# 06_-_3V3_VOLTAGE_REGULATOR.net
KiCad netlist of a schematic drawn in Altium Designer
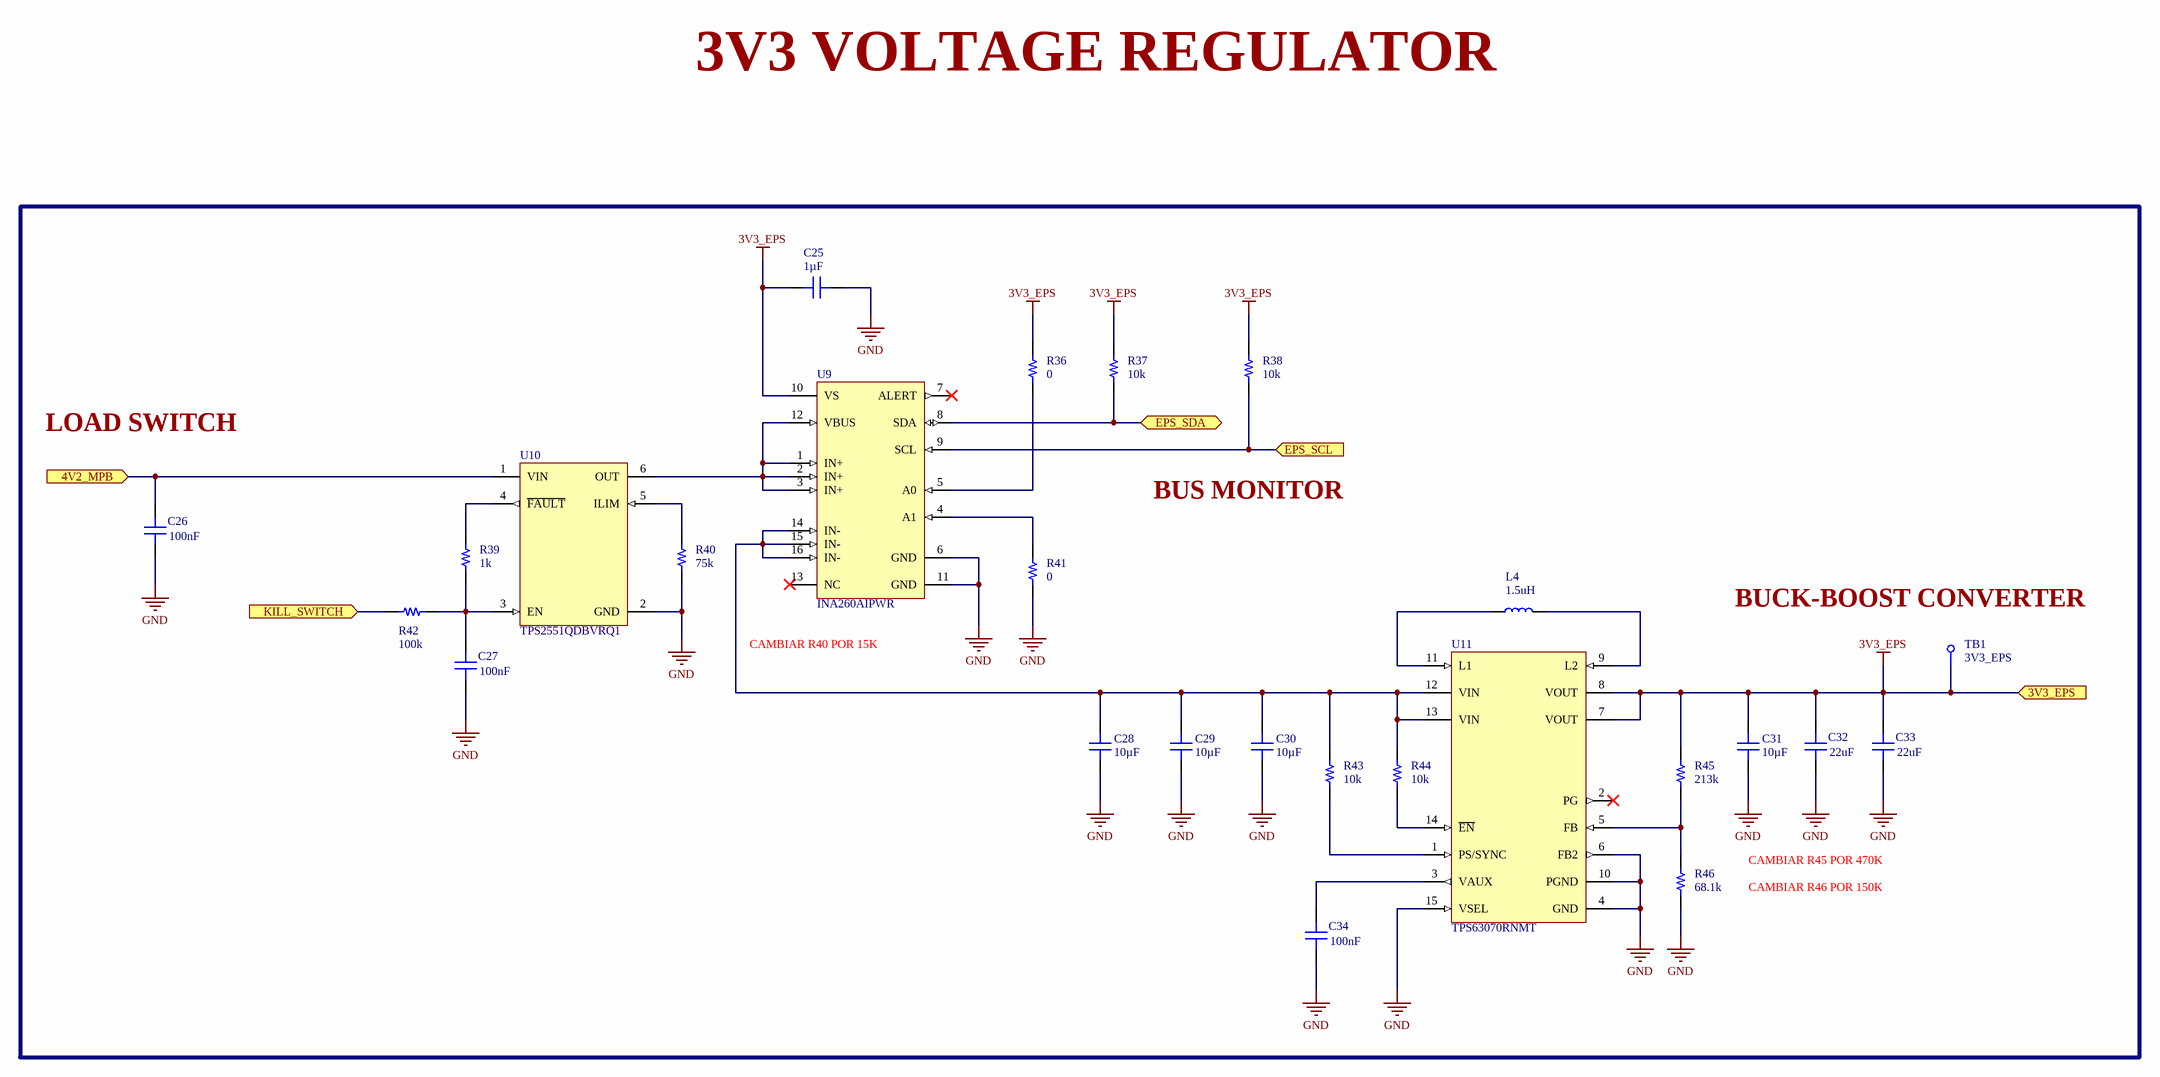
[diagram p0: [06] - 3V3 VOLTAGE REGULATOR.SchDoc]

(export (version "E")
  (design (tool "Eeschema 10.0.6"))
  (components
    (comp (ref "C25")
      (value "CL10A105KP8NNNC")
      (footprint "CAP 0603/1608")
      (description "CAP CER 1UF 10V X5R 0603")
      (fields
        (field (name "MANUFACTURER") "Samsung")
        (field (name "TOLERANCE") "10%")
        (field (name "CAPACITANCE") "1µF")
      )
      (libsource (lib "UVG") (part "CL10A105KP8NNNC"))
    )
    (comp (ref "C26")
      (value "C0603C104K8RACTU")
      (footprint "CAP 0603/1608")
      (description "CAP CER 0.1UF 10V X7R 0603")
      (fields
        (field (name "MANUFACTURER") "KEMET")
        (field (name "CAPACITANCE") "100nF")
        (field (name "TOLERANCE") "10%")
      )
      (libsource (lib "UVG") (part "C0603C104K8RACTU"))
    )
    (comp (ref "C27")
      (value "C0603C104K8RACTU")
      (footprint "CAP 0603/1608")
      (description "CAP CER 0.1UF 10V X7R 0603")
      (fields
        (field (name "MANUFACTURER") "KEMET")
        (field (name "CAPACITANCE") "100nF")
        (field (name "TOLERANCE") "10%")
      )
      (libsource (lib "UVG") (part "C0603C104K8RACTU"))
    )
    (comp (ref "C28")
      (value "LMK212BJ106KG-T")
      (footprint "CAP 0805/2012")
      (description "CAP CER 10UF 10V X5R 0805")
      (fields
        (field (name "MANUFACTURER") "Taiyo Yuden")
        (field (name "PCN PART NUMBER") "X5R, X7R Dielectrics 23/Jan/2008")
        (field (name "CAPACITANCE") "10µF")
      )
      (libsource (lib "UVG") (part "LMK212BJ106KG-T"))
    )
    (comp (ref "C29")
      (value "LMK212BJ106KG-T")
      (footprint "CAP 0805/2012")
      (description "CAP CER 10UF 10V X5R 0805")
      (fields
        (field (name "MANUFACTURER") "Taiyo Yuden")
        (field (name "PCN PART NUMBER") "X5R, X7R Dielectrics 23/Jan/2008")
        (field (name "CAPACITANCE") "10µF")
      )
      (libsource (lib "UVG") (part "LMK212BJ106KG-T"))
    )
    (comp (ref "C30")
      (value "CL10A106MQ8NNNC")
      (footprint "CAP 0603/1608")
      (description "CAP CER 10UF 6.3V X5R 0603")
      (fields
        (field (name "MANUFACTURER") "Samsung")
        (field (name "CAPACITANCE") "10µF")
        (field (name "TOLERANCE") "20%")
      )
      (libsource (lib "UVG") (part "CL10A106MQ8NNNC"))
    )
    (comp (ref "C31")
      (value "CL10A106MQ8NNNC")
      (footprint "CAP 0603/1608")
      (description "CAP CER 10UF 6.3V X5R 0603")
      (fields
        (field (name "MANUFACTURER") "Samsung")
        (field (name "CAPACITANCE") "10µF")
        (field (name "TOLERANCE") "20%")
      )
      (libsource (lib "UVG") (part "CL10A106MQ8NNNC"))
    )
    (comp (ref "C32")
      (value "CL21A226MQQNNNE")
      (footprint "CAP 0805/2012")
      (description "CAP CER 22UF 6.3V X5R 0805")
      (fields
        (field (name "MANUFACTURER") "Samsung")
        (field (name "CAPACITANCE") "22uF")
        (field (name "TOLERANCE") "20%")
      )
      (libsource (lib "UVG") (part "CL21A226MQQNNNE"))
    )
    (comp (ref "C33")
      (value "CL21A226MQQNNNE")
      (footprint "CAP 0805/2012")
      (description "CAP CER 22UF 6.3V X5R 0805")
      (fields
        (field (name "MANUFACTURER") "Samsung")
        (field (name "CAPACITANCE") "22uF")
        (field (name "TOLERANCE") "20%")
      )
      (libsource (lib "UVG") (part "CL21A226MQQNNNE"))
    )
    (comp (ref "C34")
      (value "C0603C104K8RACTU")
      (footprint "CAP 0603/1608")
      (description "CAP CER 0.1UF 10V X7R 0603")
      (fields
        (field (name "MANUFACTURER") "KEMET")
        (field (name "CAPACITANCE") "100nF")
        (field (name "TOLERANCE") "10%")
      )
      (libsource (lib "UVG") (part "C0603C104K8RACTU"))
    )
    (comp (ref "L4")
      (value "XFL4020-152MEB")
      (footprint "XFL4020")
      (description "FIXED IND 1.5UH 9.1A 15.8 MOHM SMD")
      (fields
        (field (name "MANUFACTURER") "Coilcraft")
        (field (name "TOLERANCE") "20%")
        (field (name "INDUCTANCE") "1.5uH")
      )
      (libsource (lib "UVG") (part "XFL4020-152MEB"))
    )
    (comp (ref "R36")
      (value "RMCF0603ZT0R00")
      (footprint "RES 0603/1608")
      (description "RES SMD 0 OHM JUMPER 1/10W 0603")
      (fields (field (name "MANUFACTURER") "Stackpole Electronics") (field (name "RESISTANCE") "0"))
      (libsource (lib "UVG") (part "RMCF0603ZT0R00"))
    )
    (comp (ref "R37")
      (value "RNCP0603FTD10K0")
      (footprint "RES 0603/1608")
      (description "RES SMD 10K OHM 1% 1/8W 0603")
      (fields
        (field (name "MANUFACTURER") "Stackpole Electronics")
        (field (name "RESISTANCE") "10k")
        (field (name "TOLERANCE") "1%")
      )
      (libsource (lib "UVG") (part "RNCP0603FTD10K0"))
    )
    (comp (ref "R38")
      (value "RNCP0603FTD10K0")
      (footprint "RES 0603/1608")
      (description "RES SMD 10K OHM 1% 1/8W 0603")
      (fields
        (field (name "MANUFACTURER") "Stackpole Electronics")
        (field (name "RESISTANCE") "10k")
        (field (name "TOLERANCE") "1%")
      )
      (libsource (lib "UVG") (part "RNCP0603FTD10K0"))
    )
    (comp (ref "R39")
      (value "ESR03EZPJ102")
      (footprint "RES 0603/1608")
      (description "RES SMD 1K OHM 5% 1/4W 0603")
      (fields
        (field (name "MANUFACTURER") "Rohm")
        (field (name "RESISTANCE") "1k")
        (field (name "TOLERANCE") "5%")
      )
      (libsource (lib "UVG") (part "ESR03EZPJ102"))
    )
    (comp (ref "R40")
      (value "ERJ3EKF7502V")
      (footprint "RES 0603/1608")
      (description "RES SMD 75K OHM 1% 1/10W 0603")
      (fields
        (field (name "MANUFACTURER") "Panasonic")
        (field (name "RESISTANCE") "75k")
        (field (name "TOLERANCE") "1%")
      )
      (libsource (lib "UVG") (part "ERJ3EKF7502V"))
    )
    (comp (ref "R41")
      (value "RMCF0603ZT0R00")
      (footprint "RES 0603/1608")
      (description "RES SMD 0 OHM JUMPER 1/10W 0603")
      (fields (field (name "MANUFACTURER") "Stackpole Electronics") (field (name "RESISTANCE") "0"))
      (libsource (lib "UVG") (part "RMCF0603ZT0R00"))
    )
    (comp (ref "R42")
      (value "CR0603-JW-104ELF")
      (footprint "RES 0603/1608")
      (description "RES SMD 100K OHM 5% 1/10W 0603")
      (fields
        (field (name "MANUFACTURER") "Bourns")
        (field (name "RESISTANCE") "100k")
        (field (name "TOLERANCE") "5%")
      )
      (libsource (lib "UVG") (part "CR0603-JW-104ELF"))
    )
    (comp (ref "R43")
      (value "RC0805FR-0710KL")
      (footprint "RES 0805/2012")
      (description "RES SMD 10K OHM 1% 1/8W 0805")
      (fields
        (field (name "MANUFACTURER") "Yageo")
        (field (name "RESISTANCE") "10k")
        (field (name "TOLERANCE") "1 %")
      )
      (libsource (lib "UVG") (part "RC0805FR-0710KL"))
    )
    (comp (ref "R44")
      (value "RC0805FR-0710KL")
      (footprint "RES 0805/2012")
      (description "RES SMD 10K OHM 1% 1/8W 0805")
      (fields
        (field (name "MANUFACTURER") "Yageo")
        (field (name "RESISTANCE") "10k")
        (field (name "TOLERANCE") "1 %")
      )
      (libsource (lib "UVG") (part "RC0805FR-0710KL"))
    )
    (comp (ref "R45")
      (value "RNCF0603BTE213K")
      (footprint "RES 0603/1608")
      (description "RES SMD 213K OHM 0.1% 1/10W 0603")
      (fields
        (field (name "MANUFACTURER") "Stackpole Electronics")
        (field (name "RESISTANCE") "213k")
        (field (name "TOLERANCE") "0.1%")
      )
      (libsource (lib "UVG") (part "RNCF0603BTE213K"))
    )
    (comp (ref "R46")
      (value "RMCF0603FT68K1")
      (footprint "RES 0603/1608")
      (description "RES SMD 68.1K OHM 1% 1/10W 0603")
      (fields
        (field (name "MANUFACTURER") "Stackpole Electronics")
        (field (name "RESISTANCE") "68.1k")
        (field (name "TOLERANCE") "1%")
      )
      (libsource (lib "UVG") (part "RMCF0603FT68K1"))
    )
    (comp (ref "TB1")
      (value "3V3_EPS")
      (footprint "Testpoint")
      (description "GENERIC TESTPOINT")
      (libsource (lib "UVG") (part "TESTPOINT"))
    )
    (comp (ref "U9")
      (value "INA260AIPWR")
      (footprint "TSOP65P640X120-16N")
      (description "IC MONITOR PWR/CURR 16TSSOP")
      (fields (field (name "MANUFACTURER") "Texas Instruments"))
      (libsource (lib "UVG") (part "INA260AIPWR"))
    )
    (comp (ref "U10")
      (value "TPS2551QDBVRQ1")
      (footprint "SOT23-6")
      (description "IC POWER-DIST SWITCH ADJ SOT23-6")
      (fields (field (name "MANUFACTURER") "Texas Instruments"))
      (libsource (lib "UVG") (part "TPS2551QDBVRQ1"))
    )
    (comp (ref "U11")
      (value "TPS63070RNMT")
      (footprint "15-VQFN-HR")
      (description "IC REG BCK BST ADJ 2A 15VQFN")
      (fields (field (name "MANUFACTURER") "Texas Instruments"))
      (libsource (lib "UVG") (part "TPS63070RNMT"))
    )
  )
  (nets
    (net (code "1") (name "/4V2_MPB") (class "Default")
      (node (ref "C26") (pin "2") (pinfunction "2_2") (pintype "passive"))
      (node (ref "U10") (pin "1") (pinfunction "VIN_1") (pintype "power_in"))
    )
    (net (code "2") (name "/EPS_SCL") (class "Default")
      (node (ref "R38") (pin "1") (pinfunction "1_1") (pintype "passive"))
      (node (ref "U9") (pin "9") (pinfunction "SCL_9") (pintype "input"))
    )
    (net (code "3") (name "/EPS_SDA") (class "Default")
      (node (ref "R37") (pin "1") (pinfunction "1_1") (pintype "passive"))
      (node (ref "U9") (pin "8") (pinfunction "SDA_8") (pintype "bidirectional"))
    )
    (net (code "4") (name "/KILL_SWITCH") (class "Default")
      (node (ref "R42") (pin "1") (pinfunction "1_1") (pintype "passive"))
    )
    (net (code "5") (name "3V3_EPS") (class "Default")
      (node (ref "C25") (pin "1") (pinfunction "1_1") (pintype "passive"))
      (node (ref "C31") (pin "2") (pinfunction "2_2") (pintype "passive"))
      (node (ref "C32") (pin "2") (pinfunction "2_2") (pintype "passive"))
      (node (ref "C33") (pin "2") (pinfunction "2_2") (pintype "passive"))
      (node (ref "R36") (pin "2") (pinfunction "2_2") (pintype "passive"))
      (node (ref "R37") (pin "2") (pinfunction "2_2") (pintype "passive"))
      (node (ref "R38") (pin "2") (pinfunction "2_2") (pintype "passive"))
      (node (ref "R45") (pin "2") (pinfunction "2_2") (pintype "passive"))
      (node (ref "TB1") (pin "1") (pinfunction "1_1") (pintype "passive"))
      (node (ref "U11") (pin "7") (pinfunction "VOUT_7") (pintype "power_in"))
      (node (ref "U11") (pin "8") (pinfunction "VOUT_8") (pintype "power_in"))
      (node (ref "U9") (pin "10") (pinfunction "VS_10") (pintype "power_in"))
    )
    (net (code "6") (name "GND") (class "Default")
      (node (ref "C25") (pin "2") (pinfunction "2_2") (pintype "passive"))
      (node (ref "C26") (pin "1") (pinfunction "1_1") (pintype "passive"))
      (node (ref "C27") (pin "1") (pinfunction "1_1") (pintype "passive"))
      (node (ref "C28") (pin "1") (pinfunction "1_1") (pintype "passive"))
      (node (ref "C29") (pin "1") (pinfunction "1_1") (pintype "passive"))
      (node (ref "C30") (pin "1") (pinfunction "1_1") (pintype "passive"))
      (node (ref "C31") (pin "1") (pinfunction "1_1") (pintype "passive"))
      (node (ref "C32") (pin "1") (pinfunction "1_1") (pintype "passive"))
      (node (ref "C33") (pin "1") (pinfunction "1_1") (pintype "passive"))
      (node (ref "C34") (pin "1") (pinfunction "1_1") (pintype "passive"))
      (node (ref "R40") (pin "1") (pinfunction "1_1") (pintype "passive"))
      (node (ref "R41") (pin "1") (pinfunction "1_1") (pintype "passive"))
      (node (ref "R46") (pin "1") (pinfunction "1_1") (pintype "passive"))
      (node (ref "U10") (pin "2") (pinfunction "GND_2") (pintype "power_in"))
      (node (ref "U11") (pin "10") (pinfunction "PGND_10") (pintype "power_in"))
      (node (ref "U11") (pin "15") (pinfunction "VSEL_15") (pintype "input"))
      (node (ref "U11") (pin "4") (pinfunction "GND_4") (pintype "power_in"))
      (node (ref "U11") (pin "6") (pinfunction "FB2_6") (pintype "output"))
      (node (ref "U9") (pin "11") (pinfunction "GND_11") (pintype "power_in"))
      (node (ref "U9") (pin "6") (pinfunction "GND_6") (pintype "power_in"))
    )
    (net (code "7") (name "Net-(C28-Pad2)") (class "Default")
      (node (ref "C28") (pin "2") (pinfunction "2_2") (pintype "passive"))
      (node (ref "C29") (pin "2") (pinfunction "2_2") (pintype "passive"))
      (node (ref "C30") (pin "2") (pinfunction "2_2") (pintype "passive"))
      (node (ref "R43") (pin "2") (pinfunction "2_2") (pintype "passive"))
      (node (ref "R44") (pin "2") (pinfunction "2_2") (pintype "passive"))
      (node (ref "U11") (pin "12") (pinfunction "VIN_12") (pintype "power_in"))
      (node (ref "U11") (pin "13") (pinfunction "VIN_13") (pintype "power_in"))
      (node (ref "U9") (pin "14") (pinfunction "IN-_14") (pintype "input"))
      (node (ref "U9") (pin "15") (pinfunction "IN-_15") (pintype "input"))
      (node (ref "U9") (pin "16") (pinfunction "IN-_16") (pintype "input"))
    )
    (net (code "8") (name "Net-(U9-A0)") (class "Default")
      (node (ref "R36") (pin "1") (pinfunction "1_1") (pintype "passive"))
      (node (ref "U9") (pin "5") (pinfunction "A0_5") (pintype "input"))
    )
    (net (code "9") (name "Net-(U9-A1)") (class "Default")
      (node (ref "R41") (pin "2") (pinfunction "2_2") (pintype "passive"))
      (node (ref "U9") (pin "4") (pinfunction "A1_4") (pintype "input"))
    )
    (net (code "10") (name "Net-(U10-EN)") (class "Default")
      (node (ref "C27") (pin "2") (pinfunction "2_2") (pintype "passive"))
      (node (ref "R39") (pin "1") (pinfunction "1_1") (pintype "passive"))
      (node (ref "R42") (pin "2") (pinfunction "2_2") (pintype "passive"))
      (node (ref "U10") (pin "3") (pinfunction "EN_3") (pintype "input"))
    )
    (net (code "11") (name "Net-(U10-ILIM)") (class "Default")
      (node (ref "R40") (pin "2") (pinfunction "2_2") (pintype "passive"))
      (node (ref "U10") (pin "5") (pinfunction "ILIM_5") (pintype "input"))
    )
    (net (code "12") (name "Net-(U10-OUT)") (class "Default")
      (node (ref "U10") (pin "6") (pinfunction "OUT_6") (pintype "power_in"))
      (node (ref "U9") (pin "1") (pinfunction "IN+_1") (pintype "input"))
      (node (ref "U9") (pin "12") (pinfunction "VBUS_12") (pintype "input"))
      (node (ref "U9") (pin "2") (pinfunction "IN+_2") (pintype "input"))
      (node (ref "U9") (pin "3") (pinfunction "IN+_3") (pintype "input"))
    )
    (net (code "13") (name "Net-(U10-~{FAULT})") (class "Default")
      (node (ref "R39") (pin "2") (pinfunction "2_2") (pintype "passive"))
      (node (ref "U10") (pin "4") (pinfunction "~{FAULT}_4") (pintype "output"))
    )
    (net (code "14") (name "Net-(U11-FB)") (class "Default")
      (node (ref "R45") (pin "1") (pinfunction "1_1") (pintype "passive"))
      (node (ref "R46") (pin "2") (pinfunction "2_2") (pintype "passive"))
      (node (ref "U11") (pin "5") (pinfunction "FB_5") (pintype "input"))
    )
    (net (code "15") (name "Net-(U11-L1)") (class "Default")
      (node (ref "L4") (pin "1") (pinfunction "1_1") (pintype "passive"))
      (node (ref "U11") (pin "11") (pinfunction "L1_11") (pintype "input"))
    )
    (net (code "16") (name "Net-(U11-L2)") (class "Default")
      (node (ref "L4") (pin "2") (pinfunction "2_2") (pintype "passive"))
      (node (ref "U11") (pin "9") (pinfunction "L2_9") (pintype "input"))
    )
    (net (code "17") (name "Net-(U11-PS{slash}SYNC)") (class "Default")
      (node (ref "R43") (pin "1") (pinfunction "1_1") (pintype "passive"))
      (node (ref "U11") (pin "1") (pinfunction "PS/SYNC_1") (pintype "input"))
    )
    (net (code "18") (name "Net-(U11-VAUX)") (class "Default")
      (node (ref "C34") (pin "2") (pinfunction "2_2") (pintype "passive"))
      (node (ref "U11") (pin "3") (pinfunction "VAUX_3") (pintype "output"))
    )
    (net (code "19") (name "Net-(U11-~{EN})") (class "Default")
      (node (ref "R44") (pin "1") (pinfunction "1_1") (pintype "passive"))
      (node (ref "U11") (pin "14") (pinfunction "~{EN}_14") (pintype "input"))
    )
    (net (code "20") (name "unconnected-(U9-ALERT-Pad7)") (class "Default")
      (node (ref "U9") (pin "7") (pinfunction "ALERT_7") (pintype "output+no_connect"))
    )
    (net (code "21") (name "unconnected-(U9-NC-Pad13)") (class "Default")
      (node (ref "U9") (pin "13") (pinfunction "NC_13") (pintype "passive+no_connect"))
    )
    (net (code "22") (name "unconnected-(U11-PG-Pad2)") (class "Default")
      (node (ref "U11") (pin "2") (pinfunction "PG_2") (pintype "output+no_connect"))
    )
  )
)
